# tricorder-teensy-mk-1_12.net
KiCad netlist of a schematic drawn in EAGLE
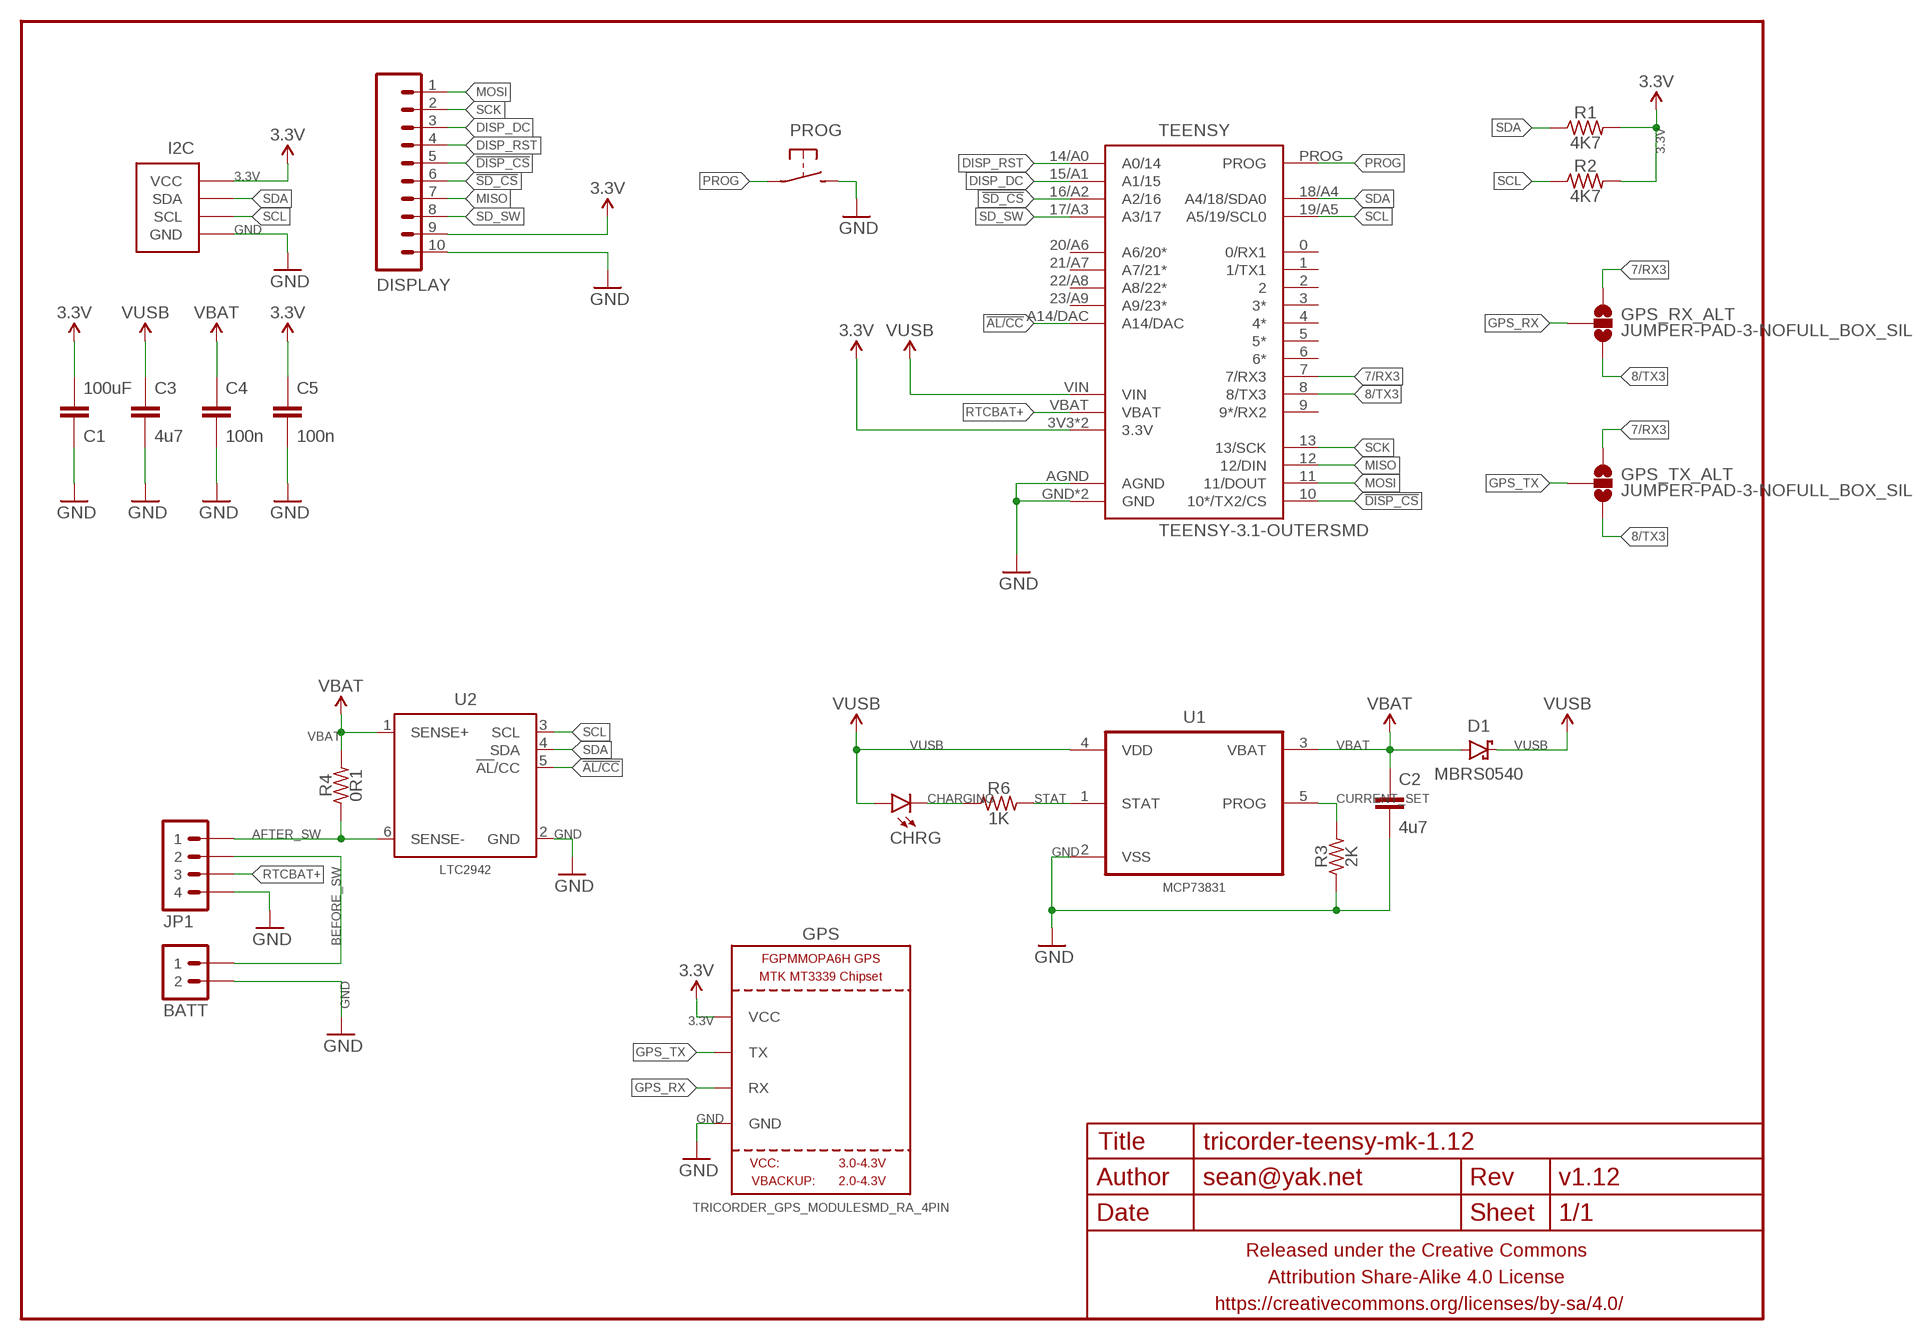
[diagram p0: schematic, sheet 1]

(export (version "E")
  (design (tool "Eeschema 10.0.6"))
  (components
    (comp (ref "BATT")
      (value "M02JST-2MM-SMT")
      (footprint "eagle-import:JST-2-SMD")
      (libsource (lib "eagle-import") (part "M02JST-2MM-SMT"))
    )
    (comp (ref "C1")
      (value "100uF")
      (footprint "eagle-import:C1210")
      (libsource (lib "eagle-import") (part "CAPACITOR-CERAMICC1210"))
    )
    (comp (ref "C2")
      (value "4u7")
      (footprint "eagle-import:C0603-TIGHTER")
      (libsource (lib "eagle-import") (part "CAPACITOR-CERAMICC0603-TIGHTER"))
    )
    (comp (ref "C3")
      (value "4u7")
      (footprint "eagle-import:C0603-TIGHTER")
      (libsource (lib "eagle-import") (part "CAPACITOR-CERAMICC0603-TIGHTER"))
    )
    (comp (ref "C4")
      (value "100n")
      (footprint "eagle-import:C0603-TIGHTER")
      (libsource (lib "eagle-import") (part "CAPACITOR-CERAMICC0603-TIGHTER"))
    )
    (comp (ref "C5")
      (value "100n")
      (footprint "eagle-import:C0603-TIGHTER")
      (libsource (lib "eagle-import") (part "CAPACITOR-CERAMICC0603-TIGHTER"))
    )
    (comp (ref "CHRG")
      (value "LED0603-TIGHT")
      (footprint "eagle-import:LED-0603-TIGHT")
      (libsource (lib "eagle-import") (part "LED0603-TIGHT"))
    )
    (comp (ref "D1")
      (value "MBRS0540")
      (footprint "eagle-import:SOD123-SCHOTTKY")
      (libsource (lib "eagle-import") (part "DIODE-SCHOTTKYSOD123"))
    )
    (comp (ref "DISPLAY")
      (value "M10SMD_RA_2MM")
      (footprint "eagle-import:1X10_SMD_RA_MALE")
      (libsource (lib "eagle-import") (part "M10SMD_RA_2MM"))
    )
    (comp (ref "FRAME1")
      (value "FRAME-LETTERNO_PACKAGE")
      (footprint "eagle-import:DUMMY")
      (fields
        (field (name "DESIGNER") "sean@yak.net")
        (field (name "VERSION") "v1.12")
        (field (name "DESIGNER_1") "sean@yak.net")
        (field (name "VERSION_1") "v1.12")
      )
      (libsource (lib "eagle-import") (part "FRAME-LETTERNO_PACKAGE"))
    )
    (comp (ref "GPS")
      (value "TRICORDER_GPS_MODULESMD_RA_4PIN")
      (footprint "eagle-import:TRICORDER_GPS_MODULE_RA_CONN_SMD_4PIN")
      (libsource (lib "eagle-import") (part "TRICORDER_GPS_MODULESMD_RA_4PIN"))
    )
    (comp (ref "GPS_RX_ALT")
      (value "JUMPER-PAD-3-NOFULL_BOX_SILK")
      (footprint "eagle-import:PAD-JUMPER-3-NO_YES_SILK_FULL_BOX")
      (libsource (lib "eagle-import") (part "JUMPER-PAD-3-NOFULL_BOX_SILK"))
    )
    (comp (ref "GPS_TX_ALT")
      (value "JUMPER-PAD-3-NOFULL_BOX_SILK")
      (footprint "eagle-import:PAD-JUMPER-3-NO_YES_SILK_FULL_BOX")
      (libsource (lib "eagle-import") (part "JUMPER-PAD-3-NOFULL_BOX_SILK"))
    )
    (comp (ref "I2C")
      (value "M04-I2CSMD_2MM_RA")
      (footprint "eagle-import:1X04_SMD_RA_2MM_I2C")
      (libsource (lib "eagle-import") (part "M04-I2CSMD_2MM_RA"))
    )
    (comp (ref "JP1")
      (value "M04SMD_RA_2MM")
      (footprint "eagle-import:1X04_SMD_RA_2MM")
      (libsource (lib "eagle-import") (part "M04SMD_RA_2MM"))
    )
    (comp (ref "PROG")
      (value "SPST-NO-TACTCK-PTS840-GK")
      (footprint "eagle-import:TACTILE-SMD-CK-PTS840-GK")
      (libsource (lib "eagle-import") (part "SPST-NO-TACTCK-PTS840-GK"))
    )
    (comp (ref "R1")
      (value "4K7")
      (footprint "eagle-import:R0603-TIGHTER")
      (libsource (lib "eagle-import") (part "RESISTORR0603-TIGHTER"))
    )
    (comp (ref "R2")
      (value "4K7")
      (footprint "eagle-import:R0603-TIGHTER")
      (libsource (lib "eagle-import") (part "RESISTORR0603-TIGHTER"))
    )
    (comp (ref "R3")
      (value "2K")
      (footprint "eagle-import:R0603-TIGHTER")
      (libsource (lib "eagle-import") (part "RESISTORR0603-TIGHTER"))
    )
    (comp (ref "R4")
      (value "0R1")
      (footprint "eagle-import:R0805-TIGHTER")
      (libsource (lib "eagle-import") (part "RESISTORR0805-TIGHTER"))
    )
    (comp (ref "R6")
      (value "1K")
      (footprint "eagle-import:R0603-TIGHTER")
      (libsource (lib "eagle-import") (part "RESISTORR0603-TIGHTER"))
    )
    (comp (ref "TEENSY")
      (value "TEENSY-3.1-OUTERSMD")
      (footprint "eagle-import:TEENSY-3.1_SMT_BOTTOM_OUTERONLY")
      (libsource (lib "eagle-import") (part "TEENSY-3.1-OUTERSMD"))
    )
    (comp (ref "U1")
      (value "MCP73831")
      (footprint "eagle-import:SOT95P280X145-5N")
      (fields (field (name "MPN") "MCP73831T-2ACI/OT"))
      (libsource (lib "eagle-import") (part "MCP73831T-2ACI/OT"))
    )
    (comp (ref "U2")
      (value "LTC2942")
      (footprint "eagle-import:DFN200X300X50-7N")
      (libsource (lib "eagle-import") (part "LTC2941/2DCB"))
    )
  )
  (nets
    (net (code "1") (name "/AFTER_SW") (class "Default")
      (node (ref "JP1") (pin "1") (pinfunction "1_1") (pintype "passive"))
      (node (ref "R4") (pin "1") (pinfunction "1_1") (pintype "passive"))
      (node (ref "U2") (pin "6") (pinfunction "SENSE-_6") (pintype "bidirectional"))
    )
    (net (code "2") (name "/BEFORE_SW") (class "Default")
      (node (ref "BATT") (pin "2") (pinfunction "1_2") (pintype "passive"))
      (node (ref "JP1") (pin "2") (pinfunction "2_2") (pintype "passive"))
    )
    (net (code "3") (name "/CHARGING") (class "Default")
      (node (ref "CHRG") (pin "C") (pinfunction "C_C") (pintype "passive"))
      (node (ref "R6") (pin "1") (pinfunction "1_1") (pintype "passive"))
    )
    (net (code "4") (name "/CURRENT_SET") (class "Default")
      (node (ref "R3") (pin "2") (pinfunction "2_2") (pintype "passive"))
      (node (ref "U1") (pin "5") (pinfunction "PROG_5") (pintype "input"))
    )
    (net (code "5") (name "/STAT") (class "Default")
      (node (ref "R6") (pin "2") (pinfunction "2_2") (pintype "passive"))
      (node (ref "U1") (pin "1") (pinfunction "STAT_1") (pintype "output"))
    )
    (net (code "6") (name "/~{AL{slash}CC}") (class "Default")
      (node (ref "TEENSY") (pin "A14/DAC") (pinfunction "A14/DAC_A14/DAC") (pintype "bidirectional"))
      (node (ref "U2") (pin "5") (pinfunction "~{AL}/CC_5") (pintype "bidirectional"))
    )
    (net (code "7") (name "/~{DISP_CS}") (class "Default")
      (node (ref "DISPLAY") (pin "5") (pinfunction "5_5") (pintype "passive"))
      (node (ref "TEENSY") (pin "10") (pinfunction "10*/TX2/CS_10") (pintype "bidirectional"))
    )
    (net (code "8") (name "/~{SD_CS}") (class "Default")
      (node (ref "DISPLAY") (pin "6") (pinfunction "6_6") (pintype "passive"))
      (node (ref "TEENSY") (pin "16/A2") (pinfunction "A2/16_16/A2") (pintype "bidirectional"))
    )
    (net (code "9") (name "3.3V") (class "Default")
      (node (ref "C1") (pin "2") (pinfunction "2_2") (pintype "passive"))
      (node (ref "C5") (pin "1") (pinfunction "1_1") (pintype "passive"))
      (node (ref "DISPLAY") (pin "9") (pinfunction "9_9") (pintype "passive"))
      (node (ref "GPS") (pin "VCC") (pinfunction "VCC_VCC") (pintype "bidirectional"))
      (node (ref "I2C") (pin "VCC") (pinfunction "VCC_VCC") (pintype "bidirectional"))
      (node (ref "R1") (pin "2") (pinfunction "2_2") (pintype "passive"))
      (node (ref "R2") (pin "2") (pinfunction "2_2") (pintype "passive"))
      (node (ref "TEENSY") (pin "3V3") (pinfunction "3.3V_3V3") (pintype "bidirectional"))
      (node (ref "TEENSY") (pin "3V3@1") (pinfunction "3.3V_3V3@1") (pintype "bidirectional"))
    )
    (net (code "10") (name "7{slash}RX3") (class "Default")
      (node (ref "GPS_RX_ALT") (pin "1") (pinfunction "1_1") (pintype "passive"))
      (node (ref "GPS_TX_ALT") (pin "1") (pinfunction "1_1") (pintype "passive"))
      (node (ref "TEENSY") (pin "7") (pinfunction "7/RX3_7") (pintype "bidirectional"))
    )
    (net (code "11") (name "8{slash}TX3") (class "Default")
      (node (ref "GPS_RX_ALT") (pin "3") (pinfunction "3_3") (pintype "passive"))
      (node (ref "GPS_TX_ALT") (pin "3") (pinfunction "3_3") (pintype "passive"))
      (node (ref "TEENSY") (pin "8") (pinfunction "8/TX3_8") (pintype "bidirectional"))
    )
    (net (code "12") (name "DISP_DC") (class "Default")
      (node (ref "DISPLAY") (pin "3") (pinfunction "3_3") (pintype "passive"))
      (node (ref "TEENSY") (pin "15/A1") (pinfunction "A1/15_15/A1") (pintype "bidirectional"))
    )
    (net (code "13") (name "DISP_RST") (class "Default")
      (node (ref "DISPLAY") (pin "4") (pinfunction "4_4") (pintype "passive"))
      (node (ref "TEENSY") (pin "14/A0") (pinfunction "A0/14_14/A0") (pintype "bidirectional"))
    )
    (net (code "14") (name "GND") (class "Default")
      (node (ref "BATT") (pin "1") (pinfunction "2_1") (pintype "passive"))
      (node (ref "C1") (pin "1") (pinfunction "1_1") (pintype "passive"))
      (node (ref "C2") (pin "2") (pinfunction "2_2") (pintype "passive"))
      (node (ref "C3") (pin "2") (pinfunction "2_2") (pintype "passive"))
      (node (ref "C4") (pin "2") (pinfunction "2_2") (pintype "passive"))
      (node (ref "C5") (pin "2") (pinfunction "2_2") (pintype "passive"))
      (node (ref "DISPLAY") (pin "10") (pinfunction "10_10") (pintype "passive"))
      (node (ref "GPS") (pin "GND") (pinfunction "GND_GND") (pintype "bidirectional"))
      (node (ref "I2C") (pin "GND") (pinfunction "GND_GND") (pintype "bidirectional"))
      (node (ref "JP1") (pin "4") (pinfunction "4_4") (pintype "passive"))
      (node (ref "PROG") (pin "3") (pinfunction "2_3") (pintype "passive"))
      (node (ref "PROG") (pin "4") (pinfunction "2_4") (pintype "passive"))
      (node (ref "R3") (pin "1") (pinfunction "1_1") (pintype "passive"))
      (node (ref "TEENSY") (pin "AGND") (pinfunction "AGND_AGND") (pintype "bidirectional"))
      (node (ref "TEENSY") (pin "GND") (pinfunction "GND_GND") (pintype "bidirectional"))
      (node (ref "TEENSY") (pin "GND@1") (pinfunction "GND_GND@1") (pintype "bidirectional"))
      (node (ref "U1") (pin "2") (pinfunction "VSS_2") (pintype "power_in"))
      (node (ref "U2") (pin "2") (pinfunction "GND_2") (pintype "bidirectional"))
    )
    (net (code "15") (name "GPS_RX") (class "Default")
      (node (ref "GPS") (pin "RX") (pinfunction "RX_RX") (pintype "bidirectional"))
      (node (ref "GPS_RX_ALT") (pin "2") (pinfunction "2_2") (pintype "passive"))
    )
    (net (code "16") (name "GPS_TX") (class "Default")
      (node (ref "GPS") (pin "TX") (pinfunction "TX_TX") (pintype "bidirectional"))
      (node (ref "GPS_TX_ALT") (pin "2") (pinfunction "2_2") (pintype "passive"))
    )
    (net (code "17") (name "MISO") (class "Default")
      (node (ref "DISPLAY") (pin "7") (pinfunction "7_7") (pintype "passive"))
      (node (ref "TEENSY") (pin "12") (pinfunction "12/DIN_12") (pintype "bidirectional"))
    )
    (net (code "18") (name "MOSI") (class "Default")
      (node (ref "DISPLAY") (pin "1") (pinfunction "1_1") (pintype "passive"))
      (node (ref "TEENSY") (pin "11") (pinfunction "11/DOUT_11") (pintype "bidirectional"))
    )
    (net (code "19") (name "PROG") (class "Default")
      (node (ref "PROG") (pin "1") (pinfunction "1_1") (pintype "passive"))
      (node (ref "PROG") (pin "2") (pinfunction "1_2") (pintype "passive"))
      (node (ref "TEENSY") (pin "PROG") (pinfunction "PROG_PROG") (pintype "bidirectional"))
    )
    (net (code "20") (name "RTCBAT+") (class "Default")
      (node (ref "JP1") (pin "3") (pinfunction "3_3") (pintype "passive"))
      (node (ref "TEENSY") (pin "VBAT") (pinfunction "VBAT_VBAT") (pintype "bidirectional"))
    )
    (net (code "21") (name "SCK") (class "Default")
      (node (ref "DISPLAY") (pin "2") (pinfunction "2_2") (pintype "passive"))
      (node (ref "TEENSY") (pin "13") (pinfunction "13/SCK_13") (pintype "bidirectional"))
    )
    (net (code "22") (name "SCL") (class "Default")
      (node (ref "I2C") (pin "SCL") (pinfunction "SCL_SCL") (pintype "bidirectional"))
      (node (ref "R2") (pin "1") (pinfunction "1_1") (pintype "passive"))
      (node (ref "TEENSY") (pin "19/A5") (pinfunction "A5/19/SCL0_19/A5") (pintype "bidirectional"))
      (node (ref "U2") (pin "3") (pinfunction "SCL_3") (pintype "bidirectional"))
    )
    (net (code "23") (name "SDA") (class "Default")
      (node (ref "I2C") (pin "SDA") (pinfunction "SDA_SDA") (pintype "bidirectional"))
      (node (ref "R1") (pin "1") (pinfunction "1_1") (pintype "passive"))
      (node (ref "TEENSY") (pin "18/A4") (pinfunction "A4/18/SDA0_18/A4") (pintype "bidirectional"))
      (node (ref "U2") (pin "4") (pinfunction "SDA_4") (pintype "bidirectional"))
    )
    (net (code "24") (name "SD_SW") (class "Default")
      (node (ref "DISPLAY") (pin "8") (pinfunction "8_8") (pintype "passive"))
      (node (ref "TEENSY") (pin "17/A3") (pinfunction "A3/17_17/A3") (pintype "bidirectional"))
    )
    (net (code "25") (name "VBAT") (class "Default")
      (node (ref "C2") (pin "1") (pinfunction "1_1") (pintype "passive"))
      (node (ref "C4") (pin "1") (pinfunction "1_1") (pintype "passive"))
      (node (ref "D1") (pin "A") (pinfunction "A_A") (pintype "passive"))
      (node (ref "R4") (pin "2") (pinfunction "2_2") (pintype "passive"))
      (node (ref "U1") (pin "3") (pinfunction "VBAT_3") (pintype "output"))
      (node (ref "U2") (pin "1") (pinfunction "SENSE+_1") (pintype "bidirectional"))
    )
    (net (code "26") (name "VUSB") (class "Default")
      (node (ref "C3") (pin "1") (pinfunction "1_1") (pintype "passive"))
      (node (ref "CHRG") (pin "A") (pinfunction "A_A") (pintype "passive"))
      (node (ref "D1") (pin "C") (pinfunction "C_C") (pintype "passive"))
      (node (ref "TEENSY") (pin "VIN") (pinfunction "VIN_VIN") (pintype "bidirectional"))
      (node (ref "U1") (pin "4") (pinfunction "VDD_4") (pintype "power_in"))
    )
    (net (code "27") (name "unconnected-(TEENSY-0{slash}RX1-Pad0)") (class "Default")
      (node (ref "TEENSY") (pin "0") (pinfunction "0/RX1_0") (pintype "bidirectional"))
    )
    (net (code "28") (name "unconnected-(TEENSY-1{slash}TX1-Pad1)") (class "Default")
      (node (ref "TEENSY") (pin "1") (pinfunction "1/TX1_1") (pintype "bidirectional"))
    )
    (net (code "29") (name "unconnected-(TEENSY-3*-Pad3)") (class "Default")
      (node (ref "TEENSY") (pin "3") (pinfunction "3*_3") (pintype "bidirectional"))
    )
    (net (code "30") (name "unconnected-(TEENSY-4*-Pad4)") (class "Default")
      (node (ref "TEENSY") (pin "4") (pinfunction "4*_4") (pintype "bidirectional"))
    )
    (net (code "31") (name "unconnected-(TEENSY-5*-Pad5)") (class "Default")
      (node (ref "TEENSY") (pin "5") (pinfunction "5*_5") (pintype "bidirectional"))
    )
    (net (code "32") (name "unconnected-(TEENSY-6*-Pad6)") (class "Default")
      (node (ref "TEENSY") (pin "6") (pinfunction "6*_6") (pintype "bidirectional"))
    )
    (net (code "33") (name "unconnected-(TEENSY-9*{slash}RX2-Pad9)") (class "Default")
      (node (ref "TEENSY") (pin "9") (pinfunction "9*/RX2_9") (pintype "bidirectional"))
    )
    (net (code "34") (name "unconnected-(TEENSY-A6{slash}20*-Pad20{slash}A6)") (class "Default")
      (node (ref "TEENSY") (pin "20/A6") (pinfunction "A6/20*_20/A6") (pintype "bidirectional"))
    )
    (net (code "35") (name "unconnected-(TEENSY-A7{slash}21*-Pad21{slash}A7)") (class "Default")
      (node (ref "TEENSY") (pin "21/A7") (pinfunction "A7/21*_21/A7") (pintype "bidirectional"))
    )
    (net (code "36") (name "unconnected-(TEENSY-A8{slash}22*-Pad22{slash}A8)") (class "Default")
      (node (ref "TEENSY") (pin "22/A8") (pinfunction "A8/22*_22/A8") (pintype "bidirectional"))
    )
    (net (code "37") (name "unconnected-(TEENSY-A9{slash}23*-Pad23{slash}A9)") (class "Default")
      (node (ref "TEENSY") (pin "23/A9") (pinfunction "A9/23*_23/A9") (pintype "bidirectional"))
    )
    (net (code "38") (name "unconnected-(TEENSY-Pad2)") (class "Default")
      (node (ref "TEENSY") (pin "2") (pinfunction "2_2") (pintype "bidirectional"))
    )
  )
)
